# schematic.net
KiCad netlist of a schematic drawn in EAGLE
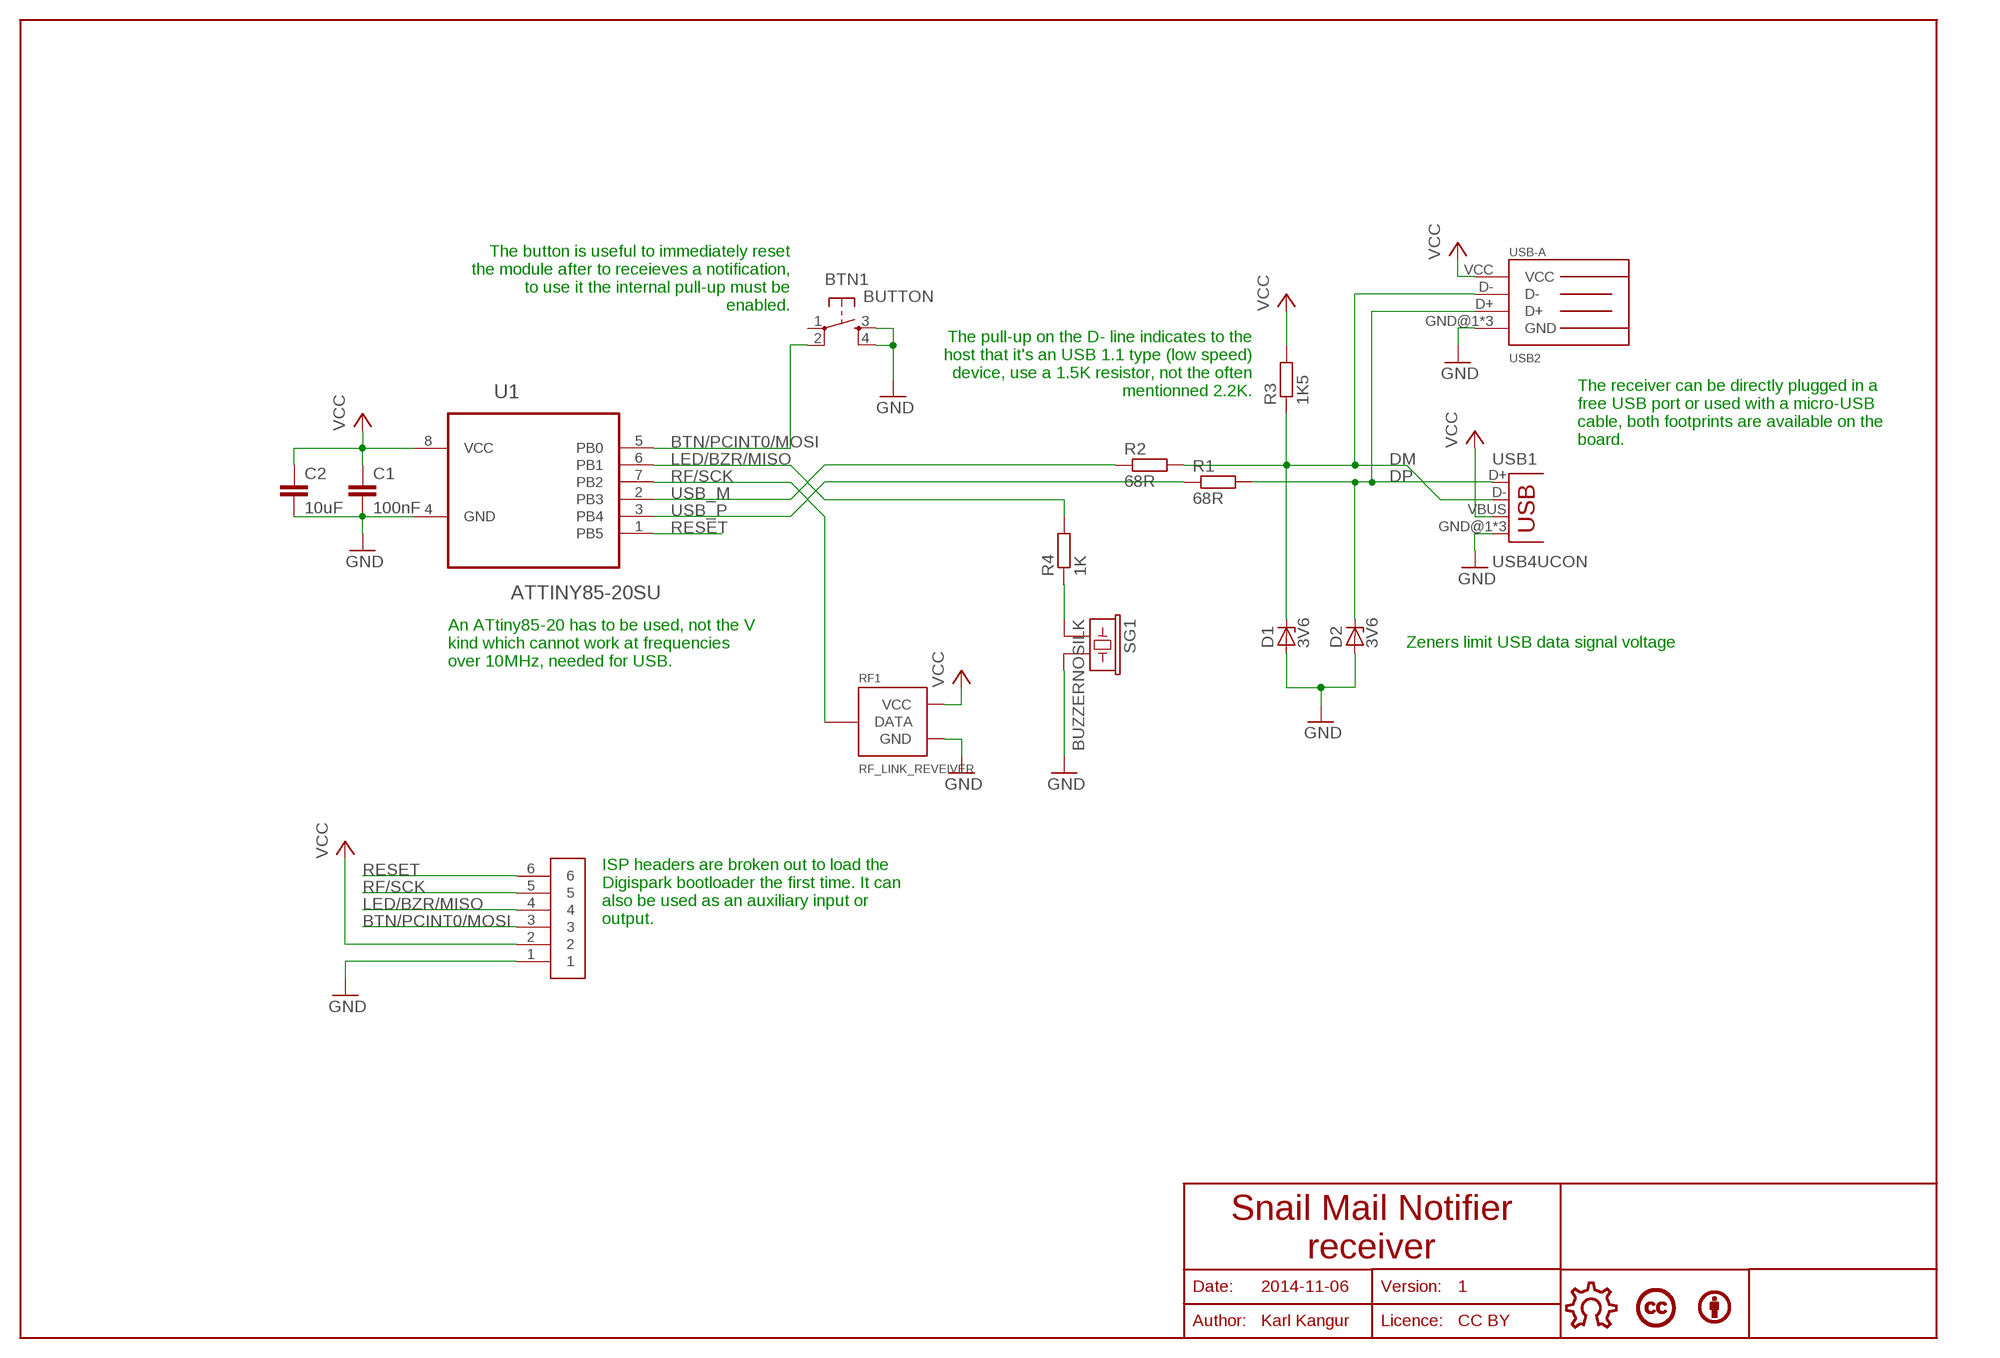
[diagram p0: schematic, sheet 1]

(export (version "E")
  (design (tool "Eeschema 10.0.6"))
  (components
    (comp (ref "BTN1")
      (value "BUTTON")
      (footprint "eagle-import:BUTTON")
      (libsource (lib "eagle-import") (part "BUTTON"))
    )
    (comp (ref "BY1")
      (value "BYBOTTOM")
      (footprint "eagle-import:BY")
      (libsource (lib "eagle-import") (part "BYBOTTOM"))
    )
    (comp (ref "C1")
      (value "100nF")
      (footprint "eagle-import:C0805")
      (libsource (lib "eagle-import") (part "C-EUC0805"))
    )
    (comp (ref "C2")
      (value "10uF")
      (footprint "eagle-import:C0805")
      (libsource (lib "eagle-import") (part "C-EUC0805"))
    )
    (comp (ref "D1")
      (value "3V6")
      (footprint "eagle-import:SOD80C")
      (libsource (lib "eagle-import") (part "ZENER-DIODESOD80C"))
    )
    (comp (ref "D2")
      (value "3V6")
      (footprint "eagle-import:SOD80C")
      (libsource (lib "eagle-import") (part "ZENER-DIODESOD80C"))
    )
    (comp (ref "LICENCE1")
      (value "LICENCECC-BOTTOM")
      (footprint "eagle-import:CREATIVE-COMMONS")
      (libsource (lib "eagle-import") (part "LICENCECC-BOTTOM"))
    )
    (comp (ref "PIN1")
      (value "PINS-6")
      (footprint "eagle-import:PINS-6")
      (libsource (lib "eagle-import") (part "PINS-6"))
    )
    (comp (ref "R1")
      (value "68R")
      (footprint "eagle-import:R0805")
      (libsource (lib "eagle-import") (part "R-EU_R0805"))
    )
    (comp (ref "R2")
      (value "68R")
      (footprint "eagle-import:R0805")
      (libsource (lib "eagle-import") (part "R-EU_R0805"))
    )
    (comp (ref "R3")
      (value "1K5")
      (footprint "eagle-import:R0805")
      (libsource (lib "eagle-import") (part "R-EU_R0805"))
    )
    (comp (ref "R4")
      (value "1K")
      (footprint "eagle-import:R0805")
      (libsource (lib "eagle-import") (part "R-EU_R0805"))
    )
    (comp (ref "RF1")
      (value "RF_LINK_REVEIVER")
      (footprint "eagle-import:RF_LINK_REVEIVER")
      (libsource (lib "eagle-import") (part "RF_LINK_REVEIVER"))
    )
    (comp (ref "SG1")
      (value "BUZZERNOSILK")
      (footprint "eagle-import:PS1240P02BT-NOSILK")
      (libsource (lib "eagle-import") (part "BUZZERNOSILK"))
    )
    (comp (ref "U$5")
      (value "OPEN-HARDWARE-LOGOBOTTOM-SMALL")
      (footprint "eagle-import:OPEN-HARDWARE-BOTTOM-SMALL")
      (libsource (lib "eagle-import") (part "OPEN-HARDWARE-LOGOBOTTOM-SMALL"))
    )
    (comp (ref "U1")
      (value "ATTINY85-20SU")
      (footprint "eagle-import:SOIC127P798X216-8N")
      (libsource (lib "eagle-import") (part "ATTINY85-20SU"))
    )
    (comp (ref "USB1")
      (value "USB4UCON")
      (footprint "eagle-import:USB-MICROB-4UCON")
      (libsource (lib "eagle-import") (part "USB4UCON"))
    )
    (comp (ref "USB2")
      (value "USB-A")
      (footprint "eagle-import:USB-A")
      (libsource (lib "eagle-import") (part "USB-A"))
    )
  )
  (nets
    (net (code "1") (name "/BTN{slash}PCINT0{slash}MOSI") (class "Default")
      (node (ref "BTN1") (pin "2") (pinfunction "2_2") (pintype "passive"))
      (node (ref "PIN1") (pin "3") (pinfunction "3_3") (pintype "bidirectional"))
      (node (ref "U1") (pin "5") (pinfunction "PB0_5") (pintype "bidirectional"))
    )
    (net (code "2") (name "/DM") (class "Default")
      (node (ref "D1") (pin "C") (pinfunction "C_C") (pintype "passive"))
      (node (ref "R2") (pin "2") (pinfunction "2_2") (pintype "passive"))
      (node (ref "R3") (pin "1") (pinfunction "1_1") (pintype "passive"))
      (node (ref "USB1") (pin "D-") (pinfunction "D-_D-") (pintype "bidirectional"))
      (node (ref "USB2") (pin "D-") (pinfunction "D-_D-") (pintype "bidirectional"))
    )
    (net (code "3") (name "/DP") (class "Default")
      (node (ref "D2") (pin "C") (pinfunction "C_C") (pintype "passive"))
      (node (ref "R1") (pin "2") (pinfunction "2_2") (pintype "passive"))
      (node (ref "USB1") (pin "D+") (pinfunction "D+_D+") (pintype "bidirectional"))
      (node (ref "USB2") (pin "D+") (pinfunction "D+_D+") (pintype "bidirectional"))
    )
    (net (code "4") (name "/LED{slash}BZR{slash}MISO") (class "Default")
      (node (ref "PIN1") (pin "4") (pinfunction "4_4") (pintype "bidirectional"))
      (node (ref "R4") (pin "2") (pinfunction "2_2") (pintype "passive"))
      (node (ref "U1") (pin "6") (pinfunction "PB1_6") (pintype "bidirectional"))
    )
    (net (code "5") (name "/RESET") (class "Default")
      (node (ref "PIN1") (pin "6") (pinfunction "6_6") (pintype "bidirectional"))
      (node (ref "U1") (pin "1") (pinfunction "PB5_1") (pintype "bidirectional"))
    )
    (net (code "6") (name "/RF{slash}SCK") (class "Default")
      (node (ref "PIN1") (pin "5") (pinfunction "5_5") (pintype "bidirectional"))
      (node (ref "RF1") (pin "DATA@1") (pinfunction "DATA_DATA@1") (pintype "bidirectional"))
      (node (ref "RF1") (pin "DATA@2") (pinfunction "DATA_DATA@2") (pintype "bidirectional"))
      (node (ref "U1") (pin "7") (pinfunction "PB2_7") (pintype "bidirectional"))
    )
    (net (code "7") (name "/USB_M") (class "Default")
      (node (ref "R2") (pin "1") (pinfunction "1_1") (pintype "passive"))
      (node (ref "U1") (pin "2") (pinfunction "PB3_2") (pintype "bidirectional"))
    )
    (net (code "8") (name "/USB_P") (class "Default")
      (node (ref "R1") (pin "1") (pinfunction "1_1") (pintype "passive"))
      (node (ref "U1") (pin "3") (pinfunction "PB4_3") (pintype "bidirectional"))
    )
    (net (code "9") (name "GND") (class "Default")
      (node (ref "BTN1") (pin "3") (pinfunction "3_3") (pintype "passive"))
      (node (ref "BTN1") (pin "4") (pinfunction "4_4") (pintype "passive"))
      (node (ref "C1") (pin "2") (pinfunction "2_2") (pintype "passive"))
      (node (ref "C2") (pin "2") (pinfunction "2_2") (pintype "passive"))
      (node (ref "D1") (pin "A") (pinfunction "A_A") (pintype "passive"))
      (node (ref "D2") (pin "A") (pinfunction "A_A") (pintype "passive"))
      (node (ref "PIN1") (pin "1") (pinfunction "1_1") (pintype "bidirectional"))
      (node (ref "RF1") (pin "GND") (pinfunction "GND_GND") (pintype "bidirectional"))
      (node (ref "SG1") (pin "P$2") (pinfunction "2_P$2") (pintype "passive"))
      (node (ref "U1") (pin "4") (pinfunction "GND_4") (pintype "passive"))
      (node (ref "USB1") (pin "GND@1") (pinfunction "GND_GND@1") (pintype "bidirectional"))
      (node (ref "USB1") (pin "GND@4") (pinfunction "GND_GND@4") (pintype "bidirectional"))
      (node (ref "USB1") (pin "GND@5") (pinfunction "GND_GND@5") (pintype "bidirectional"))
      (node (ref "USB2") (pin "GND@1") (pinfunction "GND_GND@1") (pintype "bidirectional"))
      (node (ref "USB2") (pin "GND@2") (pinfunction "GND_GND@2") (pintype "bidirectional"))
      (node (ref "USB2") (pin "GND@3") (pinfunction "GND_GND@3") (pintype "bidirectional"))
    )
    (net (code "10") (name "Net-(SG1-1)") (class "Default")
      (node (ref "R4") (pin "1") (pinfunction "1_1") (pintype "passive"))
      (node (ref "SG1") (pin "P$1") (pinfunction "1_P$1") (pintype "passive"))
    )
    (net (code "11") (name "VCC") (class "Default")
      (node (ref "C1") (pin "1") (pinfunction "1_1") (pintype "passive"))
      (node (ref "C2") (pin "1") (pinfunction "1_1") (pintype "passive"))
      (node (ref "PIN1") (pin "2") (pinfunction "2_2") (pintype "bidirectional"))
      (node (ref "R3") (pin "2") (pinfunction "2_2") (pintype "passive"))
      (node (ref "RF1") (pin "VCC") (pinfunction "VCC_VCC") (pintype "bidirectional"))
      (node (ref "U1") (pin "8") (pinfunction "VCC_8") (pintype "power_in"))
      (node (ref "USB1") (pin "VBUS") (pinfunction "VBUS_VBUS") (pintype "bidirectional"))
      (node (ref "USB2") (pin "VCC") (pinfunction "VCC_VCC") (pintype "bidirectional"))
    )
    (net (code "12") (name "unconnected-(BTN1-Pad1)") (class "Default")
      (node (ref "BTN1") (pin "1") (pinfunction "1_1") (pintype "passive"))
    )
  )
)
